# tardis.net
KiCad netlist of a schematic drawn in EAGLE
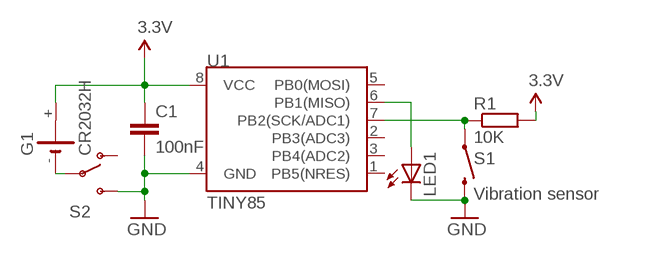
[diagram p0: schematic, sheet 1]

(export (version "E")
  (design (tool "Eeschema 10.0.6"))
  (components
    (comp (ref "C1")
      (value "100nF")
      (footprint "eagle-import:C050-030X075")
      (libsource (lib "eagle-import") (part "C-EU050-030X075"))
    )
    (comp (ref "G1")
      (value "CR2032H")
      (footprint "eagle-import:CR2032H")
      (libsource (lib "eagle-import") (part "CR2032H"))
    )
    (comp (ref "LED1")
      (value "LED3MM")
      (footprint "eagle-import:LED3MM")
      (libsource (lib "eagle-import") (part "LED3MM"))
    )
    (comp (ref "R1")
      (value "10K")
      (footprint "eagle-import:0207_10")
      (libsource (lib "eagle-import") (part "R-EU_0207/10"))
    )
    (comp (ref "S1")
      (value "Vibration sensor")
      (footprint "eagle-import:TACTILE-PTH")
      (libsource (lib "eagle-import") (part "SWITCH-MOMENTARY-2PTH"))
    )
    (comp (ref "S2")
      (value "SWITCH-SPDT-SMD-A")
      (footprint "eagle-import:SWITCH-SPST-SMD-A")
      (libsource (lib "eagle-import") (part "SWITCH-SPDT-SMD-A"))
    )
    (comp (ref "U1")
      (value "TINY85")
      (footprint "eagle-import:DIP08")
      (libsource (lib "eagle-import") (part "ATTINY45TINY45-20-DIP"))
    )
  )
  (nets
    (net (code "1") (name "3.3V") (class "Default")
      (node (ref "C1") (pin "1") (pinfunction "1_1") (pintype "passive"))
      (node (ref "G1") (pin "+") (pinfunction "+_+") (pintype "passive"))
      (node (ref "R1") (pin "2") (pinfunction "2_2") (pintype "passive"))
      (node (ref "U1") (pin "8") (pinfunction "VCC_8") (pintype "bidirectional"))
    )
    (net (code "2") (name "GND") (class "Default")
      (node (ref "C1") (pin "2") (pinfunction "2_2") (pintype "passive"))
      (node (ref "LED1") (pin "K") (pinfunction "C_K") (pintype "passive"))
      (node (ref "S1") (pin "3") (pinfunction "2_3") (pintype "passive"))
      (node (ref "S2") (pin "3") (pinfunction "S_3") (pintype "passive"))
      (node (ref "U1") (pin "4") (pinfunction "GND_4") (pintype "bidirectional"))
    )
    (net (code "3") (name "Net-(S2-P)") (class "Default")
      (node (ref "G1") (pin "-") (pinfunction "-_-") (pintype "passive"))
      (node (ref "S2") (pin "2") (pinfunction "P_2") (pintype "passive"))
    )
    (net (code "4") (name "Net-(U1-PB1(MISO))") (class "Default")
      (node (ref "LED1") (pin "A") (pinfunction "A_A") (pintype "passive"))
      (node (ref "U1") (pin "6") (pinfunction "PB1(MISO)_6") (pintype "bidirectional"))
    )
    (net (code "5") (name "Net-(U1-PB2(SCK{slash}ADC1))") (class "Default")
      (node (ref "R1") (pin "1") (pinfunction "1_1") (pintype "passive"))
      (node (ref "S1") (pin "1") (pinfunction "1_1") (pintype "passive"))
      (node (ref "U1") (pin "7") (pinfunction "PB2(SCK/ADC1)_7") (pintype "bidirectional"))
    )
    (net (code "6") (name "unconnected-(G1-+-Pad+@1)") (class "Default")
      (node (ref "G1") (pin "+@1") (pinfunction "+_+@1") (pintype "passive"))
    )
    (net (code "7") (name "unconnected-(S2-O-Pad1)") (class "Default")
      (node (ref "S2") (pin "1") (pinfunction "O_1") (pintype "passive"))
    )
    (net (code "8") (name "unconnected-(U1-PB0(MOSI)-Pad5)") (class "Default")
      (node (ref "U1") (pin "5") (pinfunction "PB0(MOSI)_5") (pintype "bidirectional"))
    )
    (net (code "9") (name "unconnected-(U1-PB3(ADC3)-Pad2)") (class "Default")
      (node (ref "U1") (pin "2") (pinfunction "PB3(ADC3)_2") (pintype "bidirectional"))
    )
    (net (code "10") (name "unconnected-(U1-PB4(ADC2)-Pad3)") (class "Default")
      (node (ref "U1") (pin "3") (pinfunction "PB4(ADC2)_3") (pintype "bidirectional"))
    )
    (net (code "11") (name "unconnected-(U1-PB5(NRES)-Pad1)") (class "Default")
      (node (ref "U1") (pin "1") (pinfunction "PB5(NRES)_1") (pintype "bidirectional"))
    )
  )
)
